# DC_Supply_Input.net
KiCad netlist of a schematic drawn in Altium Designer
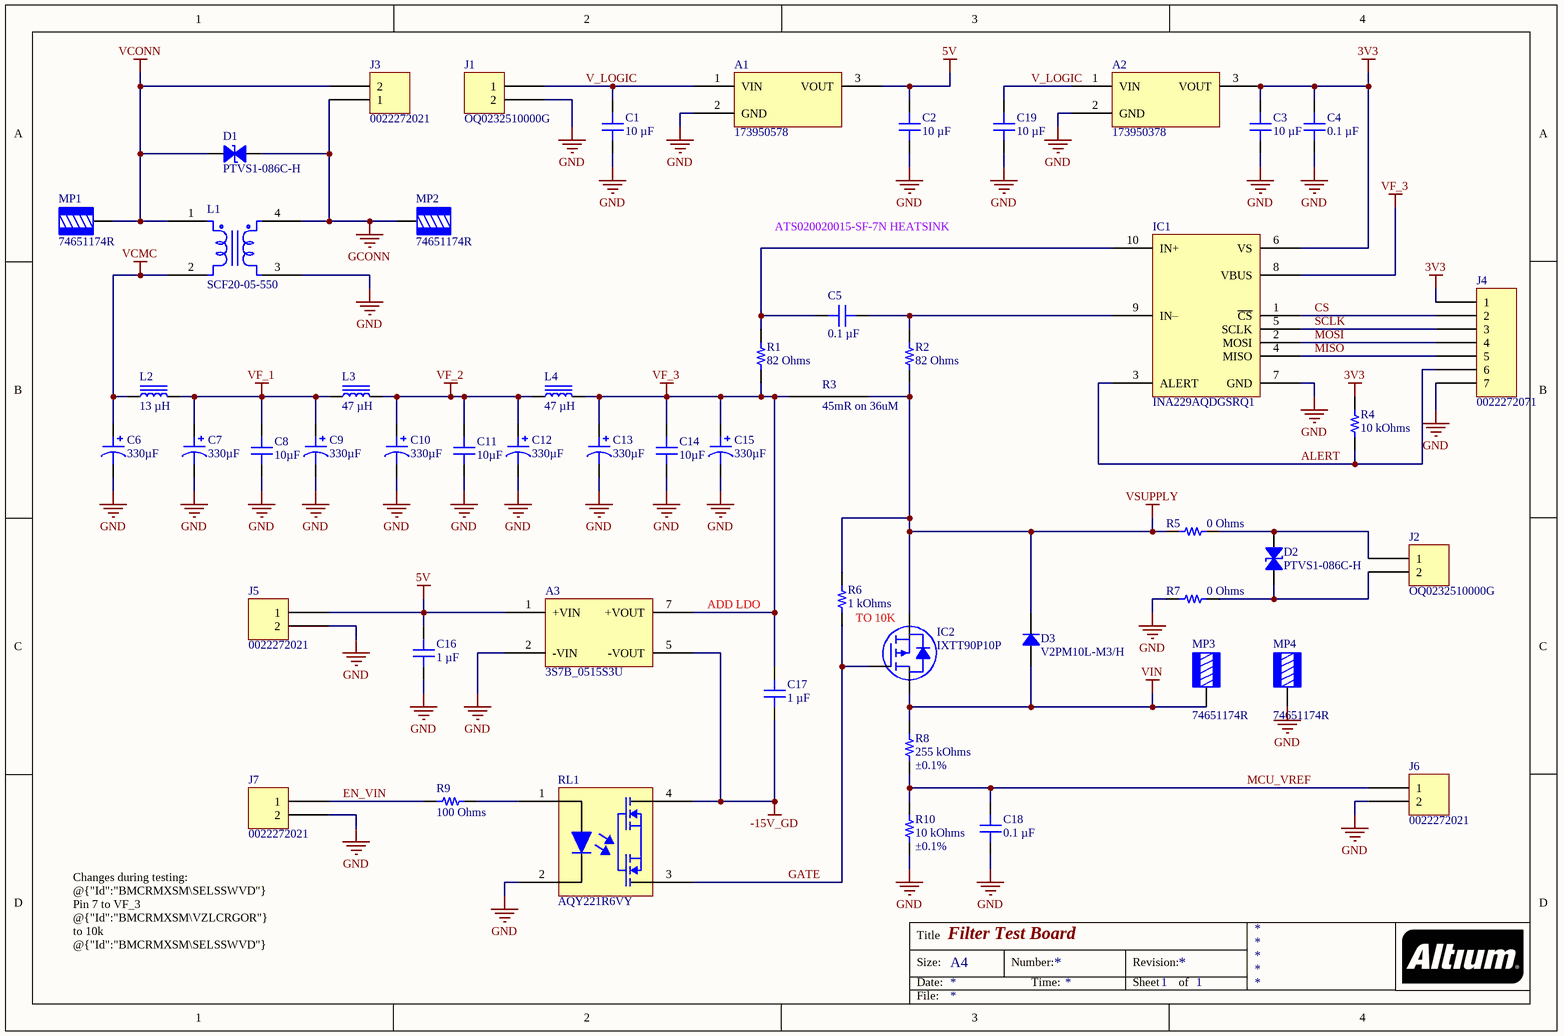
[diagram p0: DC Supply Input.SchDoc]

(export (version "E")
  (design (tool "Eeschema 10.0.6"))
  (components
    (comp (ref "A1")
      (value "173950578")
      (footprint "WURTH WPME-FDSM SIP-3 173950x78")
      (description "DC DC CONVERTER 5V 2.5W")
      (fields (field (name "MANUFACTURER") "Würth Elektronik"))
      (libsource (lib "altiumlibrary.com") (part "WURTH MAGI3C FDSM"))
    )
    (comp (ref "A2")
      (value "173950378")
      (footprint "WURTH WPME-FDSM SIP-3 173950x78")
      (description "DC DC CONVERTER 3.3V 1.65W")
      (fields (field (name "MANUFACTURER") "Würth Elektronik"))
      (libsource (lib "altiumlibrary.com") (part "WURTH MAGI3C FDSM"))
    )
    (comp (ref "A3")
      (value "3S7B_0515S3U")
      (footprint "GAPTEC 3S7B_3U SINGLE")
      (description "DC-DC")
      (fields (field (name "MANUFACTURER") "GAPTEC Electronic"))
      (libsource (lib "altiumlibrary.com") (part "GAPTEC 3S7B_3U SINGLE"))
    )
    (comp (ref "C1")
      (value "10 µF")
      (footprint "CAP 1206_3216 - 0.8MM")
      (description "CAP CER 10UF 25V X7R 1206")
      (fields
        (field (name "PART NUMBER") "CL31B106KAHNNNE")
        (field (name "MANUFACTURER") "Samsung Electro-Mechanics")
      )
      (libsource (lib "altiumlibrary.com") (part "Capacitor"))
    )
    (comp (ref "C2")
      (value "10 µF")
      (footprint "CAP 1206_3216 - 0.8MM")
      (description "CAP CER 10UF 25V X7R 1206")
      (fields
        (field (name "PART NUMBER") "CL31B106KAHNNNE")
        (field (name "MANUFACTURER") "Samsung Electro-Mechanics")
      )
      (libsource (lib "altiumlibrary.com") (part "Capacitor"))
    )
    (comp (ref "C3")
      (value "10 µF")
      (footprint "CAP 1206_3216 - 0.8MM")
      (description "CAP CER 10UF 25V X7R 1206")
      (fields
        (field (name "PART NUMBER") "CL31B106KAHNNNE")
        (field (name "MANUFACTURER") "Samsung Electro-Mechanics")
      )
      (libsource (lib "altiumlibrary.com") (part "Capacitor"))
    )
    (comp (ref "C4")
      (value "0.1 µF")
      (footprint "CAP 0603_1608")
      (description "CAP CER 0.1UF 50V X7R 0603")
      (fields
        (field (name "PART NUMBER") "CL10B104KB8NNNC")
        (field (name "MANUFACTURER") "Samsung Electro-Mechanics")
      )
      (libsource (lib "altiumlibrary.com") (part "Capacitor"))
    )
    (comp (ref "C5")
      (value "0.1 µF")
      (footprint "CAP 0603_1608")
      (description "CAP CER 0.1UF 50V X7R 0603")
      (fields
        (field (name "PART NUMBER") "CL10B104KB8NNNC")
        (field (name "MANUFACTURER") "Samsung Electro-Mechanics")
      )
      (libsource (lib "altiumlibrary.com") (part "Capacitor"))
    )
    (comp (ref "C6")
      (value "330µF")
      (footprint "CAP TH ALUM ELEC D18.00mm S7.50mm H26.50mm")
      (description "CAP ALUM 330UF 20% 160V RADIAL")
      (fields (field (name "PART NUMBER") "UCY2C331MHD6TN") (field (name "MANUFACTURER") "Nichicon"))
      (libsource (lib "altiumlibrary.com") (part "Polarised Capacitor"))
    )
    (comp (ref "C7")
      (value "330µF")
      (footprint "CAP TH ALUM ELEC D18.00mm S7.50mm H26.50mm")
      (description "CAP ALUM 330UF 20% 160V RADIAL")
      (fields (field (name "PART NUMBER") "UCY2C331MHD6TN") (field (name "MANUFACTURER") "Nichicon"))
      (libsource (lib "altiumlibrary.com") (part "Polarised Capacitor"))
    )
    (comp (ref "C8")
      (value "10µF")
      (footprint "CAP 2220_5650 2.5MM")
      (description "CAP CER 10UF 100V X7S 2220")
      (fields
        (field (name "PART NUMBER") "CGA9N3X7S2A106M230KB")
        (field (name "MANUFACTURER") "TDK Corporation")
      )
      (libsource (lib "altiumlibrary.com") (part "Capacitor"))
    )
    (comp (ref "C9")
      (value "330µF")
      (footprint "CAP TH ALUM ELEC D18.00mm S7.50mm H26.50mm")
      (description "CAP ALUM 330UF 20% 160V RADIAL")
      (fields (field (name "PART NUMBER") "UCY2C331MHD6TN") (field (name "MANUFACTURER") "Nichicon"))
      (libsource (lib "altiumlibrary.com") (part "Polarised Capacitor"))
    )
    (comp (ref "C10")
      (value "330µF")
      (footprint "CAP TH ALUM ELEC D18.00mm S7.50mm H26.50mm")
      (description "CAP ALUM 330UF 20% 160V RADIAL")
      (fields (field (name "PART NUMBER") "UCY2C331MHD6TN") (field (name "MANUFACTURER") "Nichicon"))
      (libsource (lib "altiumlibrary.com") (part "Polarised Capacitor"))
    )
    (comp (ref "C11")
      (value "10µF")
      (footprint "CAP 2220_5650 2.5MM")
      (description "CAP CER 10UF 100V X7S 2220")
      (fields
        (field (name "PART NUMBER") "CGA9N3X7S2A106M230KB")
        (field (name "MANUFACTURER") "TDK Corporation")
      )
      (libsource (lib "altiumlibrary.com") (part "Capacitor"))
    )
    (comp (ref "C12")
      (value "330µF")
      (footprint "CAP TH ALUM ELEC D18.00mm S7.50mm H26.50mm")
      (description "CAP ALUM 330UF 20% 160V RADIAL")
      (fields (field (name "PART NUMBER") "UCY2C331MHD6TN") (field (name "MANUFACTURER") "Nichicon"))
      (libsource (lib "altiumlibrary.com") (part "Polarised Capacitor"))
    )
    (comp (ref "C13")
      (value "330µF")
      (footprint "CAP TH ALUM ELEC D18.00mm S7.50mm H26.50mm")
      (description "CAP ALUM 330UF 20% 160V RADIAL")
      (fields (field (name "PART NUMBER") "UCY2C331MHD6TN") (field (name "MANUFACTURER") "Nichicon"))
      (libsource (lib "altiumlibrary.com") (part "Polarised Capacitor"))
    )
    (comp (ref "C14")
      (value "10µF")
      (footprint "CAP 2220_5650 2.5MM")
      (description "CAP CER 10UF 100V X7S 2220")
      (fields
        (field (name "PART NUMBER") "CGA9N3X7S2A106M230KB")
        (field (name "MANUFACTURER") "TDK Corporation")
      )
      (libsource (lib "altiumlibrary.com") (part "Capacitor"))
    )
    (comp (ref "C15")
      (value "330µF")
      (footprint "CAP TH ALUM ELEC D18.00mm S7.50mm H26.50mm")
      (description "CAP ALUM 330UF 20% 160V RADIAL")
      (fields (field (name "PART NUMBER") "UCY2C331MHD6TN") (field (name "MANUFACTURER") "Nichicon"))
      (libsource (lib "altiumlibrary.com") (part "Polarised Capacitor"))
    )
    (comp (ref "C16")
      (value "1 µF")
      (footprint "CAP 0603_1608")
      (description "CAP CER 1UF 25V X7R 0603")
      (fields
        (field (name "PART NUMBER") "GCM188R71E105KA64D")
        (field (name "MANUFACTURER") "Murata Electronics")
      )
      (libsource (lib "altiumlibrary.com") (part "Capacitor"))
    )
    (comp (ref "C17")
      (value "1 µF")
      (footprint "CAP 0603_1608")
      (description "CAP CER 1UF 25V X7R 0603")
      (fields
        (field (name "PART NUMBER") "GCM188R71E105KA64D")
        (field (name "MANUFACTURER") "Murata Electronics")
      )
      (libsource (lib "altiumlibrary.com") (part "Capacitor"))
    )
    (comp (ref "C18")
      (value "0.1 µF")
      (footprint "CAP 1812_4532 1.1MM")
      (description "CAP CER 0.1UF 200V C0G/NP0 1812")
      (fields (field (name "PART NUMBER") "C1812C104J2GACAUTO") (field (name "MANUFACTURER") "KEMET"))
      (libsource (lib "altiumlibrary.com") (part "Capacitor"))
    )
    (comp (ref "C19")
      (value "10 µF")
      (footprint "CAP 1206_3216 - 0.8MM")
      (description "CAP CER 10UF 25V X7R 1206")
      (fields
        (field (name "PART NUMBER") "CL31B106KAHNNNE")
        (field (name "MANUFACTURER") "Samsung Electro-Mechanics")
      )
      (libsource (lib "altiumlibrary.com") (part "Capacitor"))
    )
    (comp (ref "D1")
      (value "PTVS1-086C-H")
      (footprint "BOURNS PTSV-xxxC-H")
      (description "TVS DIODE 86VWM 99VC 2DFN")
      (fields (field (name "MANUFACTURER") "Bourns Inc."))
      (libsource (lib "altiumlibrary.com") (part "Diode TVS"))
    )
    (comp (ref "D2")
      (value "PTVS1-086C-H")
      (footprint "BOURNS PTSV-xxxC-H")
      (description "TVS DIODE 86VWM 99VC 2DFN")
      (fields (field (name "MANUFACTURER") "Bourns Inc."))
      (libsource (lib "altiumlibrary.com") (part "Diode TVS"))
    )
    (comp (ref "D3")
      (value "V2PM10L-M3/H")
      (footprint "VISHAY SMP DO-220AA")
      (description "DIODE SCHOTTKY 100V 1.9A DO220AA")
      (fields (field (name "MANUFACTURER") "Vishay General Semiconductor - Diodes Division"))
      (libsource (lib "altiumlibrary.com") (part "DIODE IPC"))
    )
    (comp (ref "IC1")
      (value "INA229AQDGSRQ1")
      (footprint "TI VSSOP-10 DGS")
      (description "IC OPAMP GP 1 CIRCUIT 10VSSOP")
      (fields (field (name "MANUFACTURER") "Texas Instruments"))
      (libsource (lib "altiumlibrary.com") (part "TI INA229"))
    )
    (comp (ref "IC2")
      (value "IXTT90P10P")
      (footprint "IXYS TO-268 P-CH GDS")
      (description "MOSFET P-CH 100V 90A TO268")
      (fields (field (name "MANUFACTURER") "IXYS"))
      (libsource (lib "altiumlibrary.com") (part "MOSFET P-CH GDS"))
    )
    (comp (ref "J1")
      (value "OQ0232510000G")
      (footprint "FCI 06-381-2PIN")
      (description "TERM BLOCK HDR 2POS 90DEG 3.81MM")
      (fields (field (name "MANUFACTURER") "Amphenol Anytek"))
      (libsource (lib "") (part "2 Pin_1"))
    )
    (comp (ref "J2")
      (value "OQ0232510000G")
      (footprint "FCI 06-381-2PIN")
      (description "TERM BLOCK HDR 2POS 90DEG 3.81MM")
      (fields (field (name "MANUFACTURER") "Amphenol Anytek"))
      (libsource (lib "") (part "2 Pin_2"))
    )
    (comp (ref "J3")
      (value "0022272021")
      (footprint "MOLEX KK 0022272021")
      (description "CONN HEADER VERT 2POS 2.54MM")
      (fields (field (name "MANUFACTURER") "Molex"))
      (libsource (lib "altiumlibrary.com") (part "2 Pin"))
    )
    (comp (ref "J4")
      (value "0022272071")
      (footprint "MOLEX KK 0022272071")
      (description "CONN HEADER VERT 7POS 2.54MM")
      (fields (field (name "MANUFACTURER") "Molex"))
      (libsource (lib "altiumlibrary.com") (part "7 Pin"))
    )
    (comp (ref "J5")
      (value "0022272021")
      (footprint "MOLEX KK 0022272021")
      (description "CONN HEADER VERT 2POS 2.54MM")
      (fields (field (name "MANUFACTURER") "Molex"))
      (libsource (lib "") (part "2 Pin_1"))
    )
    (comp (ref "J6")
      (value "0022272021")
      (footprint "MOLEX KK 0022272021")
      (description "CONN HEADER VERT 2POS 2.54MM")
      (fields (field (name "MANUFACTURER") "Molex"))
      (libsource (lib "") (part "2 Pin_2"))
    )
    (comp (ref "J7")
      (value "0022272021")
      (footprint "MOLEX KK 0022272021")
      (description "CONN HEADER VERT 2POS 2.54MM")
      (fields (field (name "MANUFACTURER") "Molex"))
      (libsource (lib "") (part "2 Pin_1"))
    )
    (comp (ref "L1")
      (value "SCF20-05-550")
      (footprint "KEMET SCF20-05-550")
      (description "CMC 5.5MH 5A 2LN TH")
      (fields (field (name "MANUFACTURER") "KEMET"))
      (libsource (lib "altiumlibrary.com") (part "KEMET SCF"))
    )
    (comp (ref "L2")
      (value "13 µH")
      (footprint "WURTH WE-HCI 1365")
      (description "FIXED IND 13UH 10A 11.2 MOHM SMD")
      (fields (field (name "PART NUMBER") "7443551131") (field (name "MANUFACTURER") "Würth Elektronik"))
      (libsource (lib "") (part "Inductor_1"))
    )
    (comp (ref "L3")
      (value "47 µH")
      (footprint "WURTH WE-HCF 14.5MM")
      (description "FIXED IND 47UH 12A 12.2 MOHM SMD")
      (fields (field (name "PART NUMBER") "7443634700") (field (name "MANUFACTURER") "Würth Elektronik"))
      (libsource (lib "altiumlibrary.com") (part "Inductor"))
    )
    (comp (ref "L4")
      (value "47 µH")
      (footprint "WURTH WE-HCF 14.5MM")
      (description "FIXED IND 47UH 12A 12.2 MOHM SMD")
      (fields (field (name "PART NUMBER") "7443634700") (field (name "MANUFACTURER") "Würth Elektronik"))
      (libsource (lib "altiumlibrary.com") (part "Inductor"))
    )
    (comp (ref "MP1")
      (value "74651174R")
      (footprint "WURTH 74651174")
      (description "TERM REDCUBE 4PIN PCB")
      (fields (field (name "MANUFACTURER") "Würth Elektronik"))
      (libsource (lib "altiumlibrary.com") (part "MOUNTING POINT"))
    )
    (comp (ref "MP2")
      (value "74651174R")
      (footprint "WURTH 74651174")
      (description "TERM REDCUBE 4PIN PCB")
      (fields (field (name "MANUFACTURER") "Würth Elektronik"))
      (libsource (lib "altiumlibrary.com") (part "MOUNTING POINT"))
    )
    (comp (ref "MP3")
      (value "74651174R")
      (footprint "WURTH 74651174")
      (description "TERM REDCUBE 4PIN PCB")
      (fields (field (name "MANUFACTURER") "Würth Elektronik"))
      (libsource (lib "altiumlibrary.com") (part "MOUNTING POINT"))
    )
    (comp (ref "MP4")
      (value "74651174R")
      (footprint "WURTH 74651174")
      (description "TERM REDCUBE 4PIN PCB")
      (fields (field (name "MANUFACTURER") "Würth Elektronik"))
      (libsource (lib "altiumlibrary.com") (part "MOUNTING POINT"))
    )
    (comp (ref "R1")
      (value "82 Ohms")
      (footprint "RES 0603_1608")
      (description "RES 82 OHM 1% 1/10W 0603")
      (fields (field (name "PART NUMBER") "RC0603FR-0782RL") (field (name "MANUFACTURER") "Yageo"))
      (libsource (lib "altiumlibrary.com") (part "Resistor"))
    )
    (comp (ref "R2")
      (value "82 Ohms")
      (footprint "RES 0603_1608")
      (description "RES 82 OHM 1% 1/10W 0603")
      (fields (field (name "PART NUMBER") "RC0603FR-0782RL") (field (name "MANUFACTURER") "Yageo"))
      (libsource (lib "altiumlibrary.com") (part "Resistor"))
    )
    (comp (ref "R3")
      (value "45mR on 36uM")
      (footprint "PCB Shunt 0.3mm x 20mm - 45mOhm on 36uM")
      (libsource (lib "Current Shunt 45mR on 36uM") (part "Current Shunt 45mR on 36uM"))
    )
    (comp (ref "R4")
      (value "10 kOhms")
      (footprint "RES 0603_1608")
      (description "RES SMD 10K OHM 0.1% 1/5W 0603")
      (fields
        (field (name "PART NUMBER") "ERJ-PB3B1002V")
        (field (name "MANUFACTURER") "Panasonic Electronic Components")
      )
      (libsource (lib "altiumlibrary.com") (part "Resistor"))
    )
    (comp (ref "R5")
      (value "0 Ohms")
      (footprint "RES 0805_2012")
      (description "RES 0 OHM JUMPER 1/8W 0805")
      (fields
        (field (name "PART NUMBER") "RMCF0805ZT0R00")
        (field (name "MANUFACTURER") "Stackpole Electronics Inc")
      )
      (libsource (lib "altiumlibrary.com") (part "Resistor"))
    )
    (comp (ref "R6")
      (value "1 kOhms")
      (footprint "RES 0805_2012")
      (description "RES SMD 1K OHM 1% 1/8W 0805")
      (fields
        (field (name "PART NUMBER") "ERJ-6ENF1001V")
        (field (name "MANUFACTURER") "Panasonic Electronic Components")
      )
      (libsource (lib "altiumlibrary.com") (part "Resistor"))
    )
    (comp (ref "R7")
      (value "0 Ohms")
      (footprint "RES 0805_2012")
      (description "RES 0 OHM JUMPER 1/8W 0805")
      (fields
        (field (name "PART NUMBER") "RMCF0805ZT0R00")
        (field (name "MANUFACTURER") "Stackpole Electronics Inc")
      )
      (libsource (lib "altiumlibrary.com") (part "Resistor"))
    )
    (comp (ref "R8")
      (value "255 kOhms")
      (footprint "RES 0603_1608")
      (description "RES SMD 255K OHM 0.1% 1/10W 0603")
      (fields
        (field (name "PART NUMBER") "ERA-3AEB2553V")
        (field (name "MANUFACTURER") "Panasonic Electronic Components")
        (field (name "TOLERANCE") "±0.1%")
      )
      (libsource (lib "altiumlibrary.com") (part "Resistor"))
    )
    (comp (ref "R9")
      (value "100 Ohms")
      (footprint "RES 0603_1608")
      (description "RES 100 OHM 1% 1/10W 0603")
      (fields (field (name "PART NUMBER") "RC0603FR-07100RL") (field (name "MANUFACTURER") "Yageo"))
      (libsource (lib "altiumlibrary.com") (part "Resistor"))
    )
    (comp (ref "R10")
      (value "10 kOhms")
      (footprint "RES 0603_1608")
      (description "RES SMD 10K OHM 0.1% 1/5W 0603")
      (fields
        (field (name "PART NUMBER") "ERJ-PB3B1002V")
        (field (name "MANUFACTURER") "Panasonic Electronic Components")
        (field (name "TOLERANCE") "±0.1%")
      )
      (libsource (lib "altiumlibrary.com") (part "Resistor"))
    )
    (comp (ref "RL1")
      (value "AQY221R6VY")
      (footprint "PANASONIC CxR10_CxR5")
      (description "SSR RELAY SPST-NO 1A 0-30V")
      (fields (field (name "MANUFACTURER") "Panasonic Electric Works"))
      (libsource (lib "altiumlibrary.com") (part "PANASONIC CxR10_CxR5"))
    )
  )
  (nets
    (net (code "1") (name "-15V_GD") (class "Default")
      (node (ref "A3") (pin "5") (pinfunction "-VOUT_5") (pintype "passive"))
      (node (ref "C17") (pin "1") (pinfunction "1_1") (pintype "passive"))
      (node (ref "RL1") (pin "4") (pinfunction "4_4") (pintype "passive"))
    )
    (net (code "2") (name "/ALERT") (class "Default")
      (node (ref "IC1") (pin "3") (pinfunction "ALERT_3") (pintype "passive"))
      (node (ref "J4") (pin "6") (pinfunction "6_6") (pintype "passive"))
      (node (ref "R4") (pin "2") (pinfunction "2_2") (pintype "passive"))
    )
    (net (code "3") (name "/CS") (class "Default")
      (node (ref "IC1") (pin "1") (pinfunction "~{CS}_1") (pintype "passive"))
      (node (ref "J4") (pin "2") (pinfunction "2_2") (pintype "passive"))
    )
    (net (code "4") (name "/EN_VIN") (class "Default")
      (node (ref "J7") (pin "1") (pinfunction "1_1") (pintype "passive"))
      (node (ref "R9") (pin "1") (pinfunction "1_1") (pintype "passive"))
    )
    (net (code "5") (name "/GATE") (class "Default")
      (node (ref "IC2") (pin "G") (pinfunction "G_G") (pintype "passive"))
      (node (ref "R6") (pin "1") (pinfunction "1_1") (pintype "passive"))
      (node (ref "RL1") (pin "3") (pinfunction "3_3") (pintype "passive"))
    )
    (net (code "6") (name "/MCU_VREF") (class "Default")
      (node (ref "C18") (pin "2") (pinfunction "2_2") (pintype "passive"))
      (node (ref "J6") (pin "1") (pinfunction "1_1") (pintype "passive"))
      (node (ref "R10") (pin "2") (pinfunction "2_2") (pintype "passive"))
      (node (ref "R8") (pin "2") (pinfunction "2_2") (pintype "passive"))
    )
    (net (code "7") (name "/MISO") (class "Default")
      (node (ref "IC1") (pin "4") (pinfunction "MISO_4") (pintype "passive"))
      (node (ref "J4") (pin "5") (pinfunction "5_5") (pintype "passive"))
    )
    (net (code "8") (name "/MOSI") (class "Default")
      (node (ref "IC1") (pin "2") (pinfunction "MOSI_2") (pintype "passive"))
      (node (ref "J4") (pin "4") (pinfunction "4_4") (pintype "passive"))
    )
    (net (code "9") (name "/SCLK") (class "Default")
      (node (ref "IC1") (pin "5") (pinfunction "SCLK_5") (pintype "passive"))
      (node (ref "J4") (pin "3") (pinfunction "3_3") (pintype "passive"))
    )
    (net (code "10") (name "/V_LOGIC") (class "Default")
      (node (ref "A1") (pin "1") (pinfunction "VIN_1") (pintype "passive"))
      (node (ref "A2") (pin "1") (pinfunction "VIN_1") (pintype "passive"))
      (node (ref "C1") (pin "2") (pinfunction "2_2") (pintype "passive"))
      (node (ref "C19") (pin "2") (pinfunction "2_2") (pintype "passive"))
      (node (ref "J1") (pin "1") (pinfunction "1_1") (pintype "passive"))
    )
    (net (code "11") (name "3V3") (class "Default")
      (node (ref "A2") (pin "3") (pinfunction "VOUT_3") (pintype "passive"))
      (node (ref "C3") (pin "2") (pinfunction "2_2") (pintype "passive"))
      (node (ref "C4") (pin "2") (pinfunction "2_2") (pintype "passive"))
      (node (ref "IC1") (pin "6") (pinfunction "VS_6") (pintype "passive"))
      (node (ref "J4") (pin "1") (pinfunction "1_1") (pintype "passive"))
      (node (ref "R4") (pin "1") (pinfunction "1_1") (pintype "passive"))
    )
    (net (code "12") (name "5V") (class "Default")
      (node (ref "A1") (pin "3") (pinfunction "VOUT_3") (pintype "passive"))
      (node (ref "A3") (pin "1") (pinfunction "+VIN_1") (pintype "passive"))
      (node (ref "C16") (pin "2") (pinfunction "2_2") (pintype "passive"))
      (node (ref "C2") (pin "2") (pinfunction "2_2") (pintype "passive"))
      (node (ref "J5") (pin "1") (pinfunction "1_1") (pintype "passive"))
    )
    (net (code "13") (name "GCONN") (class "Default")
      (node (ref "D1") (pin "2") (pinfunction "2_2") (pintype "passive"))
      (node (ref "J3") (pin "1") (pinfunction "1_1") (pintype "passive"))
      (node (ref "L1") (pin "4") (pinfunction "4_4") (pintype "passive"))
      (node (ref "MP2") (pin "1") (pinfunction "1_1") (pintype "passive"))
    )
    (net (code "14") (name "GND") (class "Default")
      (node (ref "A1") (pin "2") (pinfunction "GND_2") (pintype "passive"))
      (node (ref "A2") (pin "2") (pinfunction "GND_2") (pintype "passive"))
      (node (ref "A3") (pin "2") (pinfunction "-VIN_2") (pintype "passive"))
      (node (ref "C1") (pin "1") (pinfunction "1_1") (pintype "passive"))
      (node (ref "C10") (pin "2") (pinfunction "2_2") (pintype "passive"))
      (node (ref "C11") (pin "1") (pinfunction "1_1") (pintype "passive"))
      (node (ref "C12") (pin "2") (pinfunction "2_2") (pintype "passive"))
      (node (ref "C13") (pin "2") (pinfunction "2_2") (pintype "passive"))
      (node (ref "C14") (pin "1") (pinfunction "1_1") (pintype "passive"))
      (node (ref "C15") (pin "2") (pinfunction "2_2") (pintype "passive"))
      (node (ref "C16") (pin "1") (pinfunction "1_1") (pintype "passive"))
      (node (ref "C18") (pin "1") (pinfunction "1_1") (pintype "passive"))
      (node (ref "C19") (pin "1") (pinfunction "1_1") (pintype "passive"))
      (node (ref "C2") (pin "1") (pinfunction "1_1") (pintype "passive"))
      (node (ref "C3") (pin "1") (pinfunction "1_1") (pintype "passive"))
      (node (ref "C4") (pin "1") (pinfunction "1_1") (pintype "passive"))
      (node (ref "C6") (pin "2") (pinfunction "2_2") (pintype "passive"))
      (node (ref "C7") (pin "2") (pinfunction "2_2") (pintype "passive"))
      (node (ref "C8") (pin "1") (pinfunction "1_1") (pintype "passive"))
      (node (ref "C9") (pin "2") (pinfunction "2_2") (pintype "passive"))
      (node (ref "IC1") (pin "7") (pinfunction "GND_7") (pintype "passive"))
      (node (ref "J1") (pin "2") (pinfunction "2_2") (pintype "passive"))
      (node (ref "J4") (pin "7") (pinfunction "7_7") (pintype "passive"))
      (node (ref "J5") (pin "2") (pinfunction "2_2") (pintype "passive"))
      (node (ref "J6") (pin "2") (pinfunction "2_2") (pintype "passive"))
      (node (ref "J7") (pin "2") (pinfunction "2_2") (pintype "passive"))
      (node (ref "L1") (pin "3") (pinfunction "3_3") (pintype "passive"))
      (node (ref "MP4") (pin "1") (pinfunction "1_1") (pintype "passive"))
      (node (ref "R10") (pin "1") (pinfunction "1_1") (pintype "passive"))
      (node (ref "R7") (pin "2") (pinfunction "2_2") (pintype "passive"))
      (node (ref "RL1") (pin "2") (pinfunction "2_2") (pintype "passive"))
    )
    (net (code "15") (name "Net-(D2-Pad1)") (class "Default")
      (node (ref "D2") (pin "1") (pinfunction "1_1") (pintype "passive"))
      (node (ref "J2") (pin "1") (pinfunction "1_1") (pintype "passive"))
      (node (ref "R5") (pin "1") (pinfunction "1_1") (pintype "passive"))
    )
    (net (code "16") (name "Net-(D2-Pad2)") (class "Default")
      (node (ref "D2") (pin "2") (pinfunction "2_2") (pintype "passive"))
      (node (ref "J2") (pin "2") (pinfunction "2_2") (pintype "passive"))
      (node (ref "R7") (pin "1") (pinfunction "1_1") (pintype "passive"))
    )
    (net (code "17") (name "Net-(IC1-IN+)") (class "Default")
      (node (ref "C5") (pin "2") (pinfunction "2_2") (pintype "passive"))
      (node (ref "IC1") (pin "10") (pinfunction "IN+_10") (pintype "passive"))
      (node (ref "R1") (pin "2") (pinfunction "2_2") (pintype "passive"))
    )
    (net (code "18") (name "Net-(IC1-IN–)") (class "Default")
      (node (ref "C5") (pin "1") (pinfunction "1_1") (pintype "passive"))
      (node (ref "IC1") (pin "9") (pinfunction "IN–_9") (pintype "passive"))
      (node (ref "R2") (pin "2") (pinfunction "2_2") (pintype "passive"))
    )
    (net (code "19") (name "Net-(R9-Pad2)") (class "Default")
      (node (ref "R9") (pin "2") (pinfunction "2_2") (pintype "passive"))
      (node (ref "RL1") (pin "1") (pinfunction "1_1") (pintype "passive"))
    )
    (net (code "20") (name "VCMC") (class "Default")
      (node (ref "C6") (pin "1") (pinfunction "1_1") (pintype "passive"))
      (node (ref "L1") (pin "2") (pinfunction "2_2") (pintype "passive"))
      (node (ref "L2") (pin "2") (pinfunction "2_2") (pintype "passive"))
    )
    (net (code "21") (name "VCONN") (class "Default")
      (node (ref "D1") (pin "1") (pinfunction "1_1") (pintype "passive"))
      (node (ref "J3") (pin "2") (pinfunction "2_2") (pintype "passive"))
      (node (ref "L1") (pin "1") (pinfunction "1_1") (pintype "passive"))
      (node (ref "MP1") (pin "1") (pinfunction "1_1") (pintype "passive"))
    )
    (net (code "22") (name "VF_1") (class "Default")
      (node (ref "C7") (pin "1") (pinfunction "1_1") (pintype "passive"))
      (node (ref "C8") (pin "2") (pinfunction "2_2") (pintype "passive"))
      (node (ref "C9") (pin "1") (pinfunction "1_1") (pintype "passive"))
      (node (ref "L2") (pin "1") (pinfunction "1_1") (pintype "passive"))
      (node (ref "L3") (pin "1") (pinfunction "1_1") (pintype "passive"))
    )
    (net (code "23") (name "VF_2") (class "Default")
      (node (ref "C10") (pin "1") (pinfunction "1_1") (pintype "passive"))
      (node (ref "C11") (pin "2") (pinfunction "2_2") (pintype "passive"))
      (node (ref "C12") (pin "1") (pinfunction "1_1") (pintype "passive"))
      (node (ref "L3") (pin "2") (pinfunction "2_2") (pintype "passive"))
      (node (ref "L4") (pin "1") (pinfunction "1_1") (pintype "passive"))
    )
    (net (code "24") (name "VF_3") (class "Default")
      (node (ref "A3") (pin "7") (pinfunction "+VOUT_7") (pintype "passive"))
      (node (ref "C13") (pin "1") (pinfunction "1_1") (pintype "passive"))
      (node (ref "C14") (pin "2") (pinfunction "2_2") (pintype "passive"))
      (node (ref "C15") (pin "1") (pinfunction "1_1") (pintype "passive"))
      (node (ref "C17") (pin "2") (pinfunction "2_2") (pintype "passive"))
      (node (ref "IC1") (pin "8") (pinfunction "VBUS_8") (pintype "passive"))
      (node (ref "L4") (pin "2") (pinfunction "2_2") (pintype "passive"))
      (node (ref "R1") (pin "1") (pinfunction "1_1") (pintype "passive"))
      (node (ref "R3") (pin "2") (pinfunction "2_2") (pintype "passive"))
    )
    (net (code "25") (name "VIN") (class "Default")
      (node (ref "D3") (pin "2") (pinfunction "2_2") (pintype "passive"))
      (node (ref "IC2") (pin "D") (pinfunction "D_D") (pintype "passive"))
      (node (ref "MP3") (pin "1") (pinfunction "1_1") (pintype "passive"))
      (node (ref "R8") (pin "1") (pinfunction "1_1") (pintype "passive"))
    )
    (net (code "26") (name "VSUPPLY") (class "Default")
      (node (ref "D3") (pin "1") (pinfunction "1_1") (pintype "passive"))
      (node (ref "IC2") (pin "S") (pinfunction "S_S") (pintype "passive"))
      (node (ref "R2") (pin "1") (pinfunction "1_1") (pintype "passive"))
      (node (ref "R3") (pin "1") (pinfunction "1_1") (pintype "passive"))
      (node (ref "R5") (pin "2") (pinfunction "2_2") (pintype "passive"))
      (node (ref "R6") (pin "2") (pinfunction "2_2") (pintype "passive"))
    )
  )
)
